# Nixie_tester.net
KiCad netlist of a schematic drawn in Altium Designer
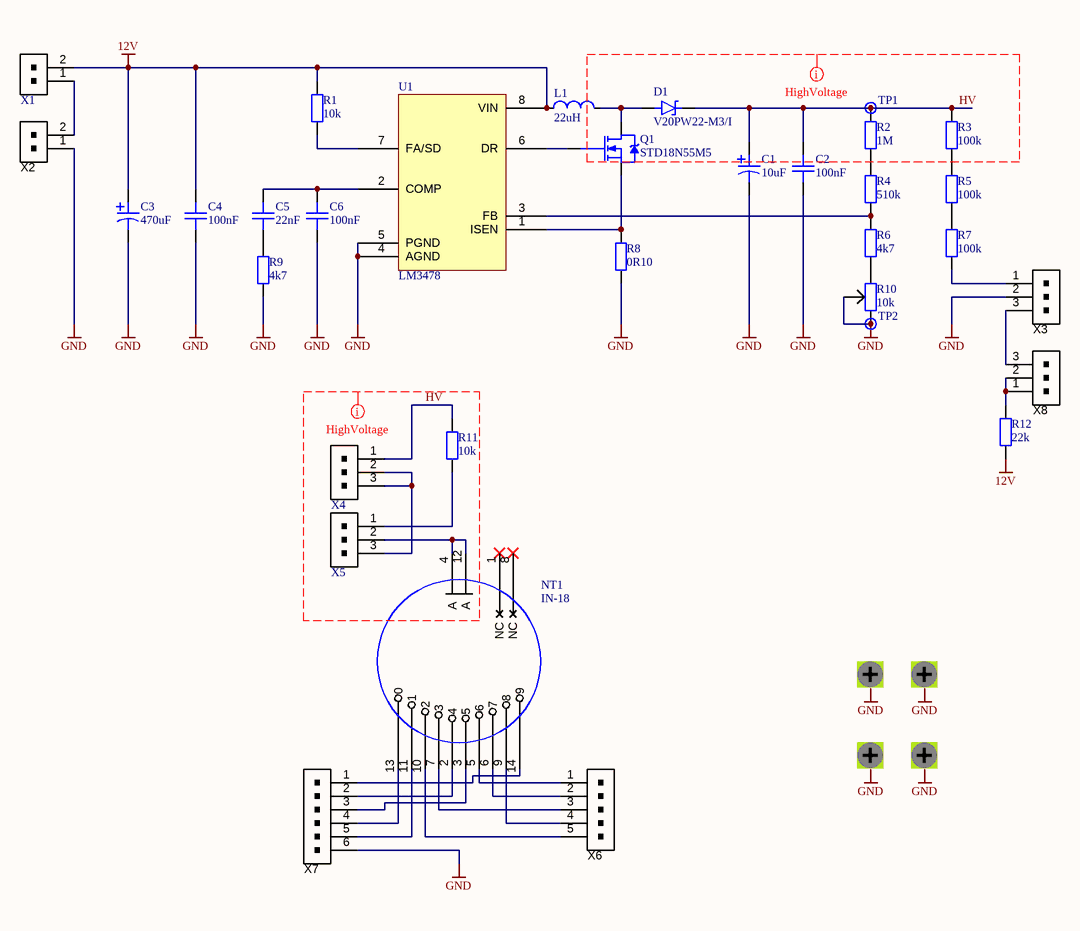
[diagram p0: Nixie tester.SchDoc]

(export (version "E")
  (design (tool "Eeschema 10.0.6"))
  (components
    (comp (ref "C1")
      (value "10uF")
      (footprint "CAP-ELCO-10mm-laying THT")
      (description "Capacitor Polar")
      (libsource (lib "MasterLib") (part "CAP - THT - 10mm"))
    )
    (comp (ref "C2")
      (value "100nF")
      (footprint "CAP-1206")
      (description "Capacitor Non-Polar")
      (libsource (lib "MasterLib") (part "CAP - 1206"))
    )
    (comp (ref "C3")
      (value "470uF")
      (footprint "CAP-Panasonic")
      (description "Capacitor Polar")
      (libsource (lib "MasterLib") (part "CAP - SMD - POL"))
    )
    (comp (ref "C4")
      (value "100nF")
      (footprint "CAP-0805")
      (description "Capacitor Non-Polar")
      (libsource (lib "MasterLib") (part "CAP - 0805"))
    )
    (comp (ref "C5")
      (value "22nF")
      (footprint "CAP-0603")
      (description "Capacitor Non-Polar")
      (libsource (lib "MasterLib") (part "CAP - 0603"))
    )
    (comp (ref "C6")
      (value "100nF")
      (footprint "CAP-0603")
      (description "Capacitor Non-Polar")
      (libsource (lib "MasterLib") (part "CAP - 0603"))
    )
    (comp (ref "D1")
      (value "V20PW22-M3/I")
      (footprint "D-DPAK (diode)")
      (description "Schottky Rectifier, 200 V, 20 A, Single, TO-252AE, 3 Pins, 960 mV")
      (libsource (lib "MasterLib") (part "D - V20PW22"))
    )
    (comp (ref "L1")
      (value "22uH")
      (footprint "IND-SMD-12.7x12.7mm")
      (description "12.7x12.7mm choke inductor")
      (libsource (lib "MasterLib") (part "IND - SMD"))
    )
    (comp (ref "MH1")
      (value "MECH - M2 screw")
      (footprint "MECH-M2 - large pad")
      (description "M3 hole with screw")
      (libsource (lib "MasterLib") (part "MECH - M2 screw"))
    )
    (comp (ref "MH2")
      (value "MECH - M2 screw")
      (footprint "MECH-M2 - large pad")
      (description "M3 hole with screw")
      (libsource (lib "MasterLib") (part "MECH - M2 screw"))
    )
    (comp (ref "MH3")
      (value "MECH - M2 screw")
      (footprint "MECH-M2 - large pad")
      (description "M3 hole with screw")
      (libsource (lib "MasterLib") (part "MECH - M2 screw"))
    )
    (comp (ref "MH4")
      (value "MECH - M2 screw")
      (footprint "MECH-M2 - large pad")
      (description "M3 hole with screw")
      (libsource (lib "MasterLib") (part "MECH - M2 screw"))
    )
    (comp (ref "NT1")
      (value "IN-18")
      (footprint "VT-IN-18 - no silk screen")
      (description "Numeric nixie tube")
      (libsource (lib "MasterLib") (part "VT - IN-18"))
    )
    (comp (ref "Q1")
      (value "STD18N55M5")
      (footprint "D-DPAK")
      (description "power N-FET")
      (libsource (lib "MasterLib") (part "T - STD18N55M5"))
    )
    (comp (ref "R1")
      (value "10k")
      (footprint "RES-0603")
      (description "Resistor")
      (libsource (lib "MasterLib") (part "RES - 0603"))
    )
    (comp (ref "R2")
      (value "1M")
      (footprint "RES-0805")
      (description "Resistor")
      (libsource (lib "MasterLib") (part "RES - 0805"))
    )
    (comp (ref "R3")
      (value "100k")
      (footprint "RES-0603")
      (description "Resistor")
      (libsource (lib "MasterLib") (part "RES - 0603"))
    )
    (comp (ref "R4")
      (value "510k")
      (footprint "RES-0805")
      (description "Resistor")
      (libsource (lib "MasterLib") (part "RES - 0805"))
    )
    (comp (ref "R5")
      (value "100k")
      (footprint "RES-0603")
      (description "Resistor")
      (libsource (lib "MasterLib") (part "RES - 0603"))
    )
    (comp (ref "R6")
      (value "4k7")
      (footprint "RES-0805")
      (description "Resistor")
      (libsource (lib "MasterLib") (part "RES - 0805"))
    )
    (comp (ref "R7")
      (value "100k")
      (footprint "RES-0603")
      (description "Resistor")
      (libsource (lib "MasterLib") (part "RES - 0603"))
    )
    (comp (ref "R8")
      (value "0R10")
      (footprint "RES-2512")
      (description "Resistor")
      (libsource (lib "MasterLib") (part "RES - 2512"))
    )
    (comp (ref "R9")
      (value "4k7")
      (footprint "RES-0603")
      (description "Resistor")
      (libsource (lib "MasterLib") (part "RES - 0603"))
    )
    (comp (ref "R10")
      (value "10k")
      (footprint "RES-TRIM-THT")
      (description "Trim Potentiometer")
      (libsource (lib "MasterLib") (part "RES - POT - TRIM - THT"))
    )
    (comp (ref "R11")
      (value "10k")
      (footprint "RES-1206")
      (description "Resistor")
      (libsource (lib "MasterLib") (part "RES - 1206"))
    )
    (comp (ref "R12")
      (value "22k")
      (footprint "RES-0603")
      (description "Resistor")
      (libsource (lib "MasterLib") (part "RES - 0603"))
    )
    (comp (ref "TP1")
      (value "MISC - Testpoint SMT")
      (footprint "MISC-TESTPOINT-SMT")
      (description "SMT testpoint")
      (libsource (lib "MasterLib") (part "MISC - Testpoint SMT"))
    )
    (comp (ref "TP2")
      (value "MISC - Testpoint SMT")
      (footprint "MISC-TESTPOINT-SMT")
      (description "SMT testpoint")
      (libsource (lib "MasterLib") (part "MISC - Testpoint SMT"))
    )
    (comp (ref "U1")
      (value "LM3478")
      (footprint "IC-SOIC-8")
      (description "2.97~40V Wide Input Range Boost/SEPIC/Flyback DC-DC Controller")
      (libsource (lib "MasterLib") (part "IC - LM3478"))
    )
    (comp (ref "X1")
      (value "CONN - 2P -THT-JST 2.00mm")
      (footprint "CONN-2P-THT-STRAIGHT-JST 2.00mm")
      (description "1x2 pin THT connector")
      (libsource (lib "MasterLib") (part "CONN - 2P -THT-JST 2.00mm"))
    )
    (comp (ref "X2")
      (value "CONN - PWR")
      (footprint "CONN-POWER")
      (description "5.5/2.1/9.5mm DC táp, anya")
      (libsource (lib "MasterLib") (part "CONN - PWR"))
    )
    (comp (ref "X3")
      (value "CONN - 3P - THT-JST 1.5mm")
      (footprint "CONN-3P-THT-JST 1.5mm")
      (description "1x3 pin header")
      (libsource (lib "") (part "CONN - 3P - THT-JST 1.5mm_1"))
    )
    (comp (ref "X4")
      (value "CONN - 3P -THT-JST 2.5mm")
      (footprint "CONN-3P-THT-STRAIGHT-JST 2.5mm")
      (description "1x3 pin THT connector")
      (libsource (lib "MasterLib") (part "CONN - 3P -THT-JST 2.5mm"))
    )
    (comp (ref "X5")
      (value "CONN - 3P -THT-JST 2.5mm")
      (footprint "CONN-3P-THT-STRAIGHT-JST 2.5mm")
      (description "1x3 pin THT connector")
      (libsource (lib "MasterLib") (part "CONN - 3P -THT-JST 2.5mm"))
    )
    (comp (ref "X6")
      (value "CONN - 5P - THT-JST 1.5mm")
      (footprint "CONN-5P-THT-STRAIGHT-JST 1.5mm")
      (description "1x5 pin header")
      (libsource (lib "MasterLib") (part "CONN - 5P - THT-JST 1.5mm"))
    )
    (comp (ref "X7")
      (value "CONN - 6P - THT-JST 1.5mm")
      (footprint "CONN-6P-THT-STRAIGHT-JST 1.5mm")
      (description "1x6 pin header")
      (libsource (lib "MasterLib") (part "CONN - 6P - THT-JST 1.5mm"))
    )
    (comp (ref "X8")
      (value "CONN - 3P - THT-JST 1.5mm")
      (footprint "CONN-3P-THT-JST 1.5mm")
      (description "1x3 pin header")
      (libsource (lib "MasterLib") (part "CONN - 3P - THT-JST 1.5mm"))
    )
  )
  (nets
    (net (code "1") (name "/HV") (class "Default")
      (node (ref "C1") (pin "2") (pinfunction "2_2") (pintype "passive"))
      (node (ref "C2") (pin "2") (pinfunction "2_2") (pintype "passive"))
      (node (ref "D1") (pin "2") (pinfunction "2_2") (pintype "passive"))
      (node (ref "R11") (pin "2") (pinfunction "2_2") (pintype "passive"))
      (node (ref "R2") (pin "2") (pinfunction "2_2") (pintype "passive"))
      (node (ref "R3") (pin "2") (pinfunction "2_2") (pintype "passive"))
      (node (ref "TP1") (pin "1") (pinfunction "1_1") (pintype "passive"))
      (node (ref "X4") (pin "1") (pinfunction "1_1") (pintype "passive"))
    )
    (net (code "2") (name "12V") (class "Default")
      (node (ref "C3") (pin "2") (pinfunction "2_2") (pintype "passive"))
      (node (ref "C4") (pin "2") (pinfunction "2_2") (pintype "passive"))
      (node (ref "L1") (pin "1") (pinfunction "1_1") (pintype "passive"))
      (node (ref "R1") (pin "2") (pinfunction "2_2") (pintype "passive"))
      (node (ref "R12") (pin "1") (pinfunction "1_1") (pintype "passive"))
      (node (ref "U1") (pin "8") (pinfunction "VIN_8") (pintype "passive"))
      (node (ref "X1") (pin "2") (pinfunction "2_2") (pintype "passive"))
    )
    (net (code "3") (name "GND") (class "Default")
      (node (ref "C1") (pin "1") (pinfunction "1_1") (pintype "passive"))
      (node (ref "C2") (pin "1") (pinfunction "1_1") (pintype "passive"))
      (node (ref "C3") (pin "1") (pinfunction "1_1") (pintype "passive"))
      (node (ref "C4") (pin "1") (pinfunction "1_1") (pintype "passive"))
      (node (ref "C6") (pin "1") (pinfunction "1_1") (pintype "passive"))
      (node (ref "MH1") (pin "MH") (pinfunction "Con_MH") (pintype "passive"))
      (node (ref "MH2") (pin "MH") (pinfunction "Con_MH") (pintype "passive"))
      (node (ref "MH3") (pin "MH") (pinfunction "Con_MH") (pintype "passive"))
      (node (ref "MH4") (pin "MH") (pinfunction "Con_MH") (pintype "passive"))
      (node (ref "R10") (pin "2") (pinfunction "2_2") (pintype "passive"))
      (node (ref "R10") (pin "3") (pinfunction "3_3") (pintype "passive"))
      (node (ref "R8") (pin "1") (pinfunction "1_1") (pintype "passive"))
      (node (ref "R9") (pin "1") (pinfunction "1_1") (pintype "passive"))
      (node (ref "TP2") (pin "1") (pinfunction "1_1") (pintype "passive"))
      (node (ref "U1") (pin "4") (pinfunction "AGND_4") (pintype "passive"))
      (node (ref "U1") (pin "5") (pinfunction "PGND_5") (pintype "passive"))
      (node (ref "X2") (pin "1") (pinfunction "1_1") (pintype "passive"))
      (node (ref "X3") (pin "2") (pinfunction "2_2") (pintype "passive"))
      (node (ref "X7") (pin "6") (pinfunction "6_6") (pintype "passive"))
    )
    (net (code "4") (name "Net-(C5-Pad1)") (class "Default")
      (node (ref "C5") (pin "1") (pinfunction "1_1") (pintype "passive"))
      (node (ref "R9") (pin "2") (pinfunction "2_2") (pintype "passive"))
    )
    (net (code "5") (name "Net-(NT1-0)") (class "Default")
      (node (ref "NT1") (pin "13") (pinfunction "0_13") (pintype "passive"))
      (node (ref "X7") (pin "4") (pinfunction "4_4") (pintype "passive"))
    )
    (net (code "6") (name "Net-(NT1-1)") (class "Default")
      (node (ref "NT1") (pin "11") (pinfunction "1_11") (pintype "passive"))
      (node (ref "X7") (pin "5") (pinfunction "5_5") (pintype "passive"))
    )
    (net (code "7") (name "Net-(NT1-2)") (class "Default")
      (node (ref "NT1") (pin "10") (pinfunction "2_10") (pintype "passive"))
      (node (ref "X6") (pin "5") (pinfunction "5_5") (pintype "passive"))
    )
    (net (code "8") (name "Net-(NT1-3)") (class "Default")
      (node (ref "NT1") (pin "7") (pinfunction "3_7") (pintype "passive"))
      (node (ref "X6") (pin "3") (pinfunction "3_3") (pintype "passive"))
    )
    (net (code "9") (name "Net-(NT1-4)") (class "Default")
      (node (ref "NT1") (pin "2") (pinfunction "4_2") (pintype "passive"))
      (node (ref "X7") (pin "2") (pinfunction "2_2") (pintype "passive"))
    )
    (net (code "10") (name "Net-(NT1-5)") (class "Default")
      (node (ref "NT1") (pin "3") (pinfunction "5_3") (pintype "passive"))
      (node (ref "X7") (pin "3") (pinfunction "3_3") (pintype "passive"))
    )
    (net (code "11") (name "Net-(NT1-6)") (class "Default")
      (node (ref "NT1") (pin "5") (pinfunction "6_5") (pintype "passive"))
      (node (ref "X6") (pin "1") (pinfunction "1_1") (pintype "passive"))
    )
    (net (code "12") (name "Net-(NT1-7)") (class "Default")
      (node (ref "NT1") (pin "6") (pinfunction "7_6") (pintype "passive"))
      (node (ref "X6") (pin "2") (pinfunction "2_2") (pintype "passive"))
    )
    (net (code "13") (name "Net-(NT1-8)") (class "Default")
      (node (ref "NT1") (pin "9") (pinfunction "8_9") (pintype "passive"))
      (node (ref "X6") (pin "4") (pinfunction "4_4") (pintype "passive"))
    )
    (net (code "14") (name "Net-(NT1-9)") (class "Default")
      (node (ref "NT1") (pin "14") (pinfunction "9_14") (pintype "passive"))
      (node (ref "X7") (pin "1") (pinfunction "1_1") (pintype "passive"))
    )
    (net (code "15") (name "Net-(NT1-A-Pad12)") (class "Default")
      (node (ref "NT1") (pin "12") (pinfunction "A_12") (pintype "passive"))
      (node (ref "NT1") (pin "4") (pinfunction "A_4") (pintype "passive"))
      (node (ref "X5") (pin "2") (pinfunction "2_2") (pintype "passive"))
    )
    (net (code "16") (name "Net-(Q1-D)") (class "Default")
      (node (ref "D1") (pin "1") (pinfunction "1_1") (pintype "passive"))
      (node (ref "L1") (pin "2") (pinfunction "2_2") (pintype "passive"))
      (node (ref "Q1") (pin "3") (pinfunction "D_3") (pintype "passive"))
    )
    (net (code "17") (name "Net-(Q1-G)") (class "Default")
      (node (ref "Q1") (pin "1") (pinfunction "G_1") (pintype "passive"))
      (node (ref "U1") (pin "6") (pinfunction "DR_6") (pintype "passive"))
    )
    (net (code "18") (name "Net-(Q1-S)") (class "Default")
      (node (ref "Q1") (pin "2") (pinfunction "S_2") (pintype "passive"))
      (node (ref "R8") (pin "2") (pinfunction "2_2") (pintype "passive"))
      (node (ref "U1") (pin "1") (pinfunction "ISEN_1") (pintype "passive"))
    )
    (net (code "19") (name "Net-(R2-Pad1)") (class "Default")
      (node (ref "R2") (pin "1") (pinfunction "1_1") (pintype "passive"))
      (node (ref "R4") (pin "2") (pinfunction "2_2") (pintype "passive"))
    )
    (net (code "20") (name "Net-(R3-Pad1)") (class "Default")
      (node (ref "R3") (pin "1") (pinfunction "1_1") (pintype "passive"))
      (node (ref "R5") (pin "2") (pinfunction "2_2") (pintype "passive"))
    )
    (net (code "21") (name "Net-(R5-Pad1)") (class "Default")
      (node (ref "R5") (pin "1") (pinfunction "1_1") (pintype "passive"))
      (node (ref "R7") (pin "2") (pinfunction "2_2") (pintype "passive"))
    )
    (net (code "22") (name "Net-(R7-Pad1)") (class "Default")
      (node (ref "R7") (pin "1") (pinfunction "1_1") (pintype "passive"))
      (node (ref "X3") (pin "1") (pinfunction "1_1") (pintype "passive"))
    )
    (net (code "23") (name "Net-(R10-Pad1)") (class "Default")
      (node (ref "R10") (pin "1") (pinfunction "1_1") (pintype "passive"))
      (node (ref "R6") (pin "1") (pinfunction "1_1") (pintype "passive"))
    )
    (net (code "24") (name "Net-(R11-Pad1)") (class "Default")
      (node (ref "R11") (pin "1") (pinfunction "1_1") (pintype "passive"))
      (node (ref "X5") (pin "1") (pinfunction "1_1") (pintype "passive"))
    )
    (net (code "25") (name "Net-(R12-Pad2)") (class "Default")
      (node (ref "R12") (pin "2") (pinfunction "2_2") (pintype "passive"))
      (node (ref "X8") (pin "1") (pinfunction "1_1") (pintype "passive"))
      (node (ref "X8") (pin "2") (pinfunction "2_2") (pintype "passive"))
    )
    (net (code "26") (name "Net-(U1-COMP)") (class "Default")
      (node (ref "C5") (pin "2") (pinfunction "2_2") (pintype "passive"))
      (node (ref "C6") (pin "2") (pinfunction "2_2") (pintype "passive"))
      (node (ref "U1") (pin "2") (pinfunction "COMP_2") (pintype "passive"))
    )
    (net (code "27") (name "Net-(U1-FA{slash}SD)") (class "Default")
      (node (ref "R1") (pin "1") (pinfunction "1_1") (pintype "passive"))
      (node (ref "U1") (pin "7") (pinfunction "FA/SD_7") (pintype "passive"))
    )
    (net (code "28") (name "Net-(U1-FB)") (class "Default")
      (node (ref "R4") (pin "1") (pinfunction "1_1") (pintype "passive"))
      (node (ref "R6") (pin "2") (pinfunction "2_2") (pintype "passive"))
      (node (ref "U1") (pin "3") (pinfunction "FB_3") (pintype "passive"))
    )
    (net (code "29") (name "Net-(X1-Pad1)") (class "Default")
      (node (ref "X1") (pin "1") (pinfunction "1_1") (pintype "passive"))
      (node (ref "X2") (pin "2") (pinfunction "2_2") (pintype "passive"))
    )
    (net (code "30") (name "Net-(X3-Pad3)") (class "Default")
      (node (ref "X3") (pin "3") (pinfunction "3_3") (pintype "passive"))
      (node (ref "X8") (pin "3") (pinfunction "3_3") (pintype "passive"))
    )
    (net (code "31") (name "Net-(X4-Pad2)") (class "Default")
      (node (ref "X4") (pin "2") (pinfunction "2_2") (pintype "passive"))
      (node (ref "X4") (pin "3") (pinfunction "3_3") (pintype "passive"))
      (node (ref "X5") (pin "3") (pinfunction "3_3") (pintype "passive"))
    )
    (net (code "32") (name "unconnected-(NT1-NC-Pad1)") (class "Default")
      (node (ref "NT1") (pin "1") (pinfunction "NC_1") (pintype "passive+no_connect"))
    )
    (net (code "33") (name "unconnected-(NT1-NC-Pad8)") (class "Default")
      (node (ref "NT1") (pin "8") (pinfunction "NC_8") (pintype "passive+no_connect"))
    )
  )
)
